# pifan.net
KiCad netlist of a schematic drawn in EAGLE
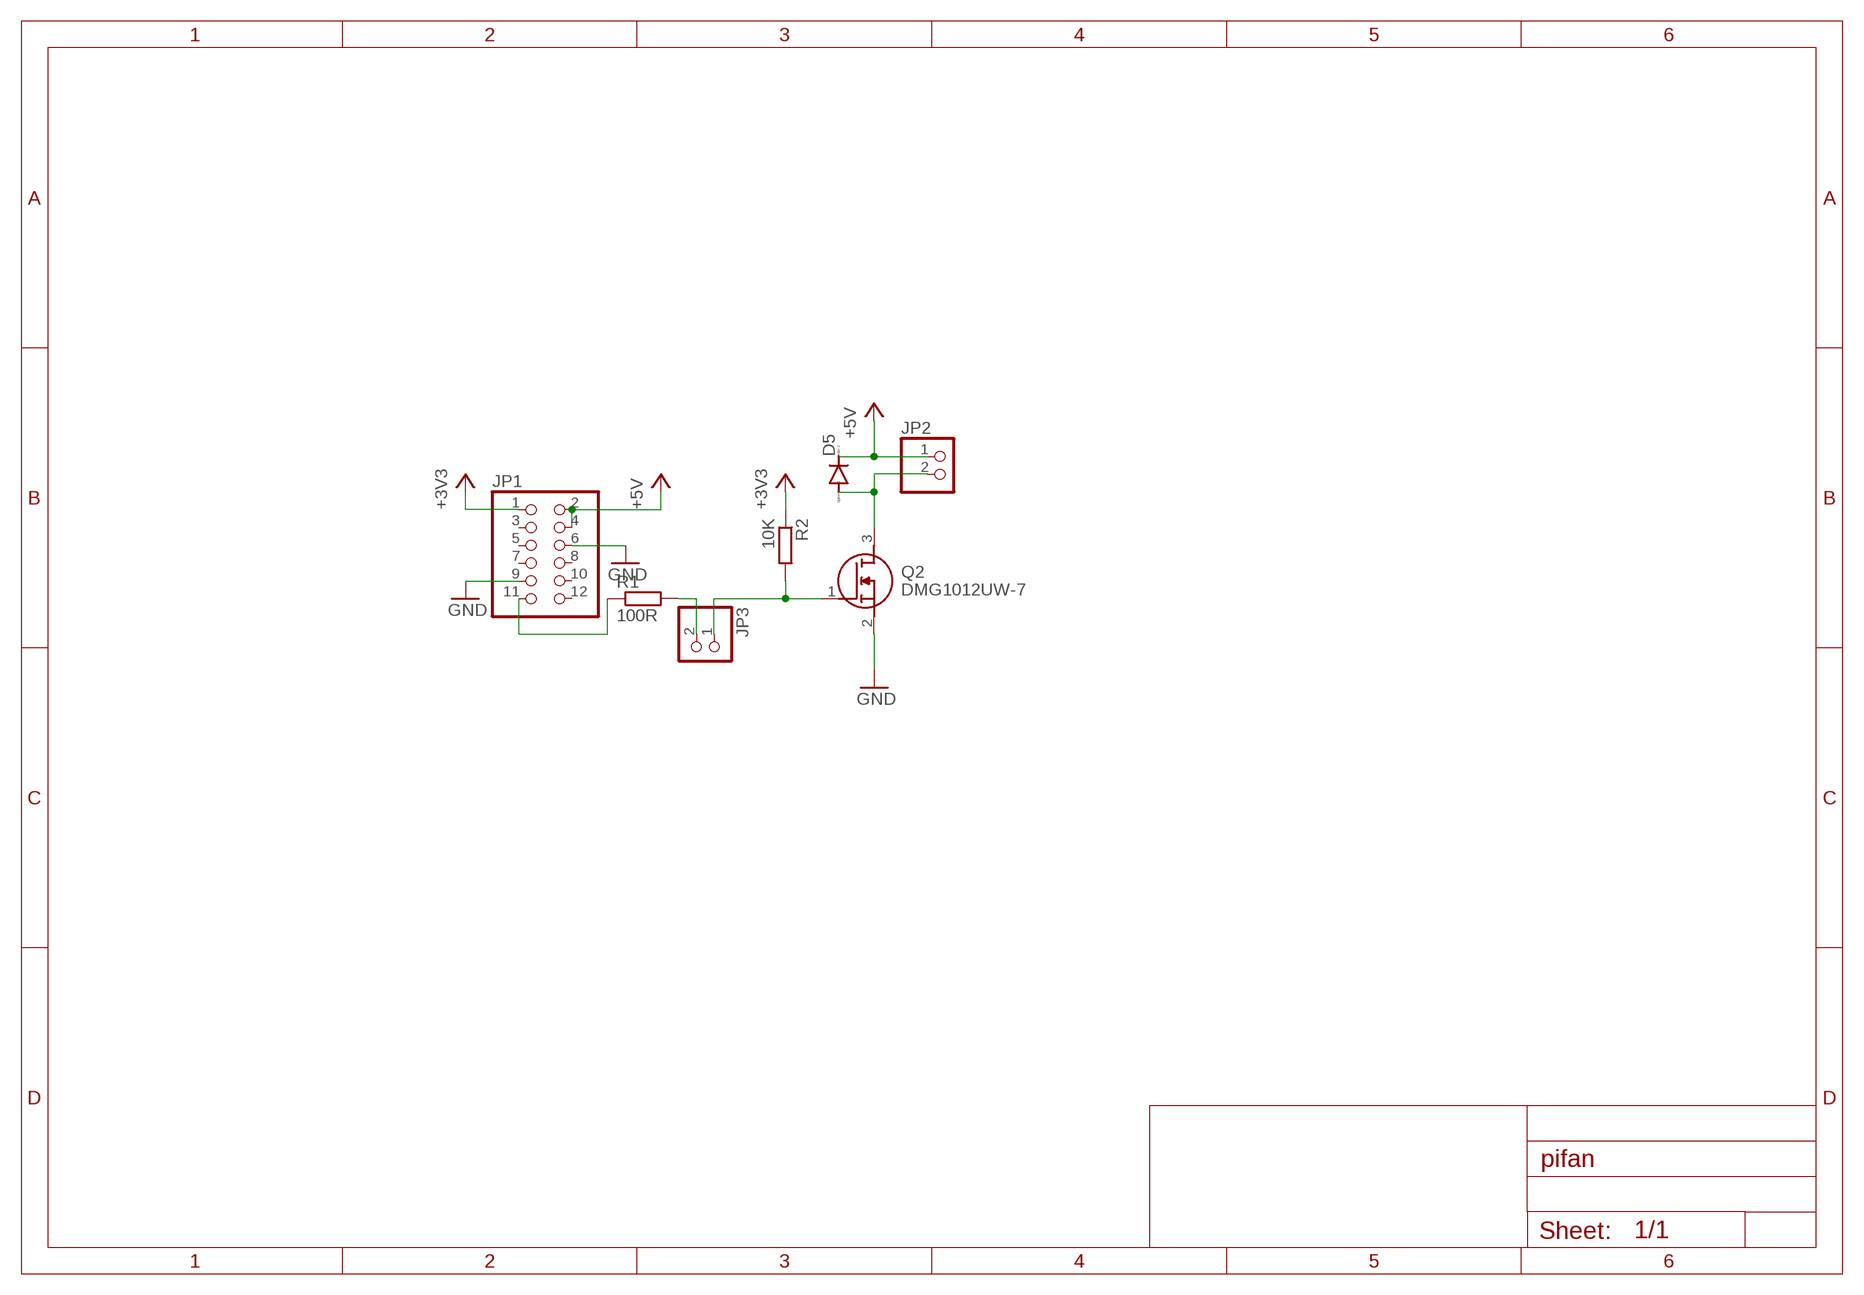
[diagram p0: schematic, sheet 1]

(export (version "E")
  (design (tool "Eeschema 10.0.6"))
  (components
    (comp (ref "D5")
      (value "DIODE-SOD123")
      (footprint "eagle-import:SOD123")
      (libsource (lib "eagle-import") (part "DIODE-SOD123"))
    )
    (comp (ref "JP1")
      (value "PINHD-2X6")
      (footprint "eagle-import:2X06")
      (libsource (lib "eagle-import") (part "PINHD-2X6"))
    )
    (comp (ref "JP2")
      (value "PINHD-1X2")
      (footprint "eagle-import:1X02")
      (libsource (lib "eagle-import") (part "pinhead_325_PINHD-1X2"))
    )
    (comp (ref "JP3")
      (value "PINHD-1X21X02SQUARE")
      (footprint "eagle-import:1X02SQUARE")
      (libsource (lib "eagle-import") (part "PINHD-1X21X02SQUARE"))
    )
    (comp (ref "Q2")
      (value "DMG1012UW-7")
      (footprint "eagle-import:SOT65P210X100-3N")
      (fields (field (name "MOUSER_PART_NUMBER") "621-DMG1012UW-7"))
      (libsource (lib "eagle-import") (part "DMG1012UW-7"))
    )
    (comp (ref "R1")
      (value "100R")
      (footprint "eagle-import:R0805")
      (libsource (lib "eagle-import") (part "R-EU_R0805"))
    )
    (comp (ref "R2")
      (value "10K")
      (footprint "eagle-import:R0805")
      (libsource (lib "eagle-import") (part "R-EU_R0805"))
    )
  )
  (nets
    (net (code "1") (name "+3V3") (class "Default")
      (node (ref "JP1") (pin "1") (pinfunction "1_1") (pintype "passive"))
      (node (ref "R2") (pin "1") (pinfunction "1_1") (pintype "passive"))
    )
    (net (code "2") (name "+5V") (class "Default")
      (node (ref "D5") (pin "C") (pinfunction "C_C") (pintype "passive"))
      (node (ref "JP1") (pin "2") (pinfunction "2_2") (pintype "passive"))
      (node (ref "JP1") (pin "4") (pinfunction "4_4") (pintype "passive"))
      (node (ref "JP2") (pin "1") (pinfunction "1_1") (pintype "passive"))
    )
    (net (code "3") (name "GND") (class "Default")
      (node (ref "JP1") (pin "6") (pinfunction "6_6") (pintype "passive"))
      (node (ref "JP1") (pin "9") (pinfunction "9_9") (pintype "passive"))
      (node (ref "Q2") (pin "2") (pinfunction "S_2") (pintype "bidirectional"))
    )
    (net (code "4") (name "Net-(JP1-Pad11)") (class "Default")
      (node (ref "JP1") (pin "11") (pinfunction "11_11") (pintype "passive"))
      (node (ref "R1") (pin "1") (pinfunction "1_1") (pintype "passive"))
    )
    (net (code "5") (name "Net-(JP3-Pad2)") (class "Default")
      (node (ref "JP3") (pin "2") (pinfunction "2_2") (pintype "passive"))
      (node (ref "R1") (pin "2") (pinfunction "2_2") (pintype "passive"))
    )
    (net (code "6") (name "Net-(Q2-D)") (class "Default")
      (node (ref "D5") (pin "A") (pinfunction "A_A") (pintype "passive"))
      (node (ref "JP2") (pin "2") (pinfunction "2_2") (pintype "passive"))
      (node (ref "Q2") (pin "3") (pinfunction "D_3") (pintype "bidirectional"))
    )
    (net (code "7") (name "Net-(Q2-G)") (class "Default")
      (node (ref "JP3") (pin "1") (pinfunction "1_1") (pintype "passive"))
      (node (ref "Q2") (pin "1") (pinfunction "G_1") (pintype "bidirectional"))
      (node (ref "R2") (pin "2") (pinfunction "2_2") (pintype "passive"))
    )
    (net (code "8") (name "unconnected-(JP1-Pad3)") (class "Default")
      (node (ref "JP1") (pin "3") (pinfunction "3_3") (pintype "passive"))
    )
    (net (code "9") (name "unconnected-(JP1-Pad5)") (class "Default")
      (node (ref "JP1") (pin "5") (pinfunction "5_5") (pintype "passive"))
    )
    (net (code "10") (name "unconnected-(JP1-Pad7)") (class "Default")
      (node (ref "JP1") (pin "7") (pinfunction "7_7") (pintype "passive"))
    )
    (net (code "11") (name "unconnected-(JP1-Pad8)") (class "Default")
      (node (ref "JP1") (pin "8") (pinfunction "8_8") (pintype "passive"))
    )
    (net (code "12") (name "unconnected-(JP1-Pad10)") (class "Default")
      (node (ref "JP1") (pin "10") (pinfunction "10_10") (pintype "passive"))
    )
    (net (code "13") (name "unconnected-(JP1-Pad12)") (class "Default")
      (node (ref "JP1") (pin "12") (pinfunction "12_12") (pintype "passive"))
    )
  )
)
